# ColonRelay.net
KiCad netlist of a schematic drawn in EAGLE
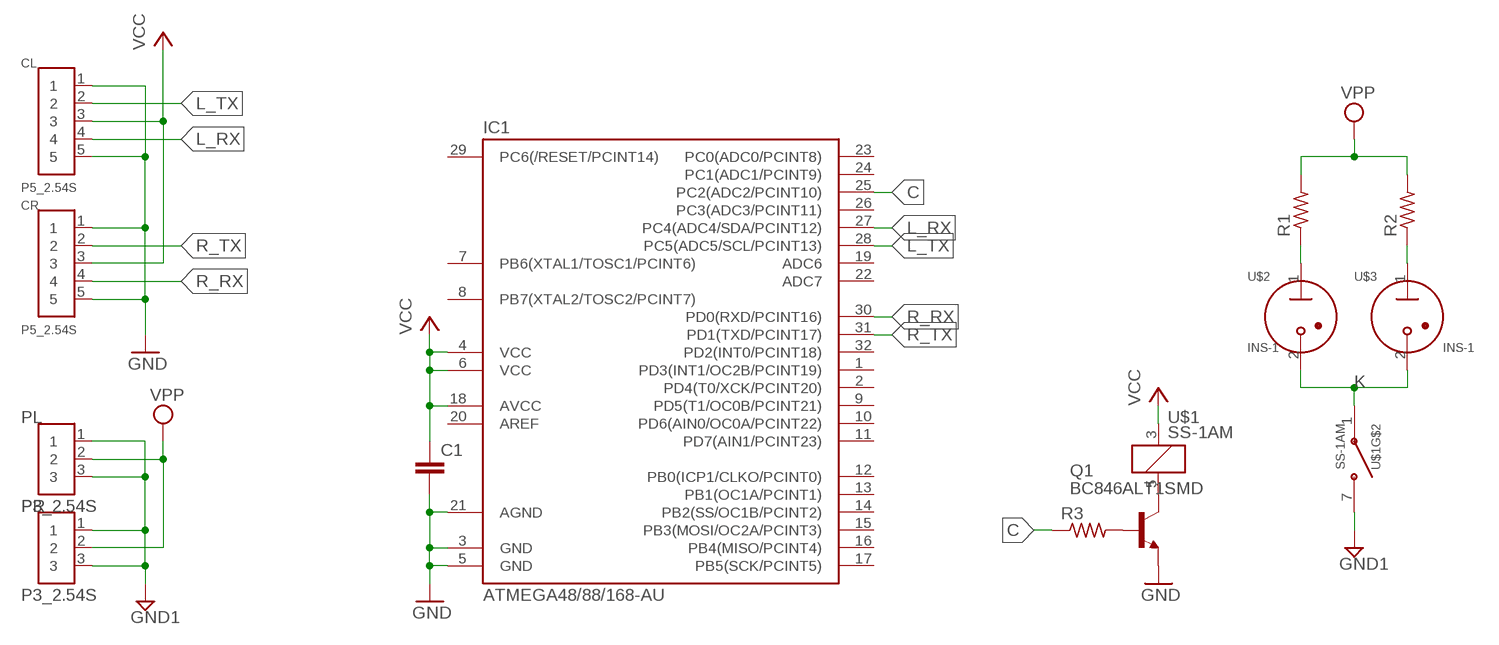
[diagram p0: schematic, sheet 1]

(export (version "E")
  (design (tool "Eeschema 10.0.6"))
  (components
    (comp (ref "C1")
      (value "C-EUC0603K")
      (footprint "eagle-import:C0603K")
      (libsource (lib "eagle-import") (part "C-EUC0603K"))
    )
    (comp (ref "CL")
      (value "P5_2.54S")
      (footprint "eagle-import:P5_2.54S")
      (libsource (lib "eagle-import") (part "P5_2.54S"))
    )
    (comp (ref "CR")
      (value "P5_2.54S")
      (footprint "eagle-import:P5_2.54S")
      (libsource (lib "eagle-import") (part "P5_2.54S"))
    )
    (comp (ref "IC1")
      (value "ATMEGA48/88/168-AU")
      (footprint "eagle-import:TQFP32-08")
      (libsource (lib "eagle-import") (part "ATMEGA48/88/168-AU"))
    )
    (comp (ref "PL")
      (value "P3_2.54S")
      (footprint "eagle-import:P3_2.54S")
      (libsource (lib "eagle-import") (part "P3_2.54S"))
    )
    (comp (ref "PR")
      (value "P3_2.54S")
      (footprint "eagle-import:P3_2.54S")
      (libsource (lib "eagle-import") (part "P3_2.54S"))
    )
    (comp (ref "Q1")
      (value "BC846ALT1SMD")
      (footprint "eagle-import:SOT23")
      (libsource (lib "eagle-import") (part "BC846SMDALT1"))
    )
    (comp (ref "R1")
      (value "R-US_R1206")
      (footprint "eagle-import:R1206")
      (libsource (lib "eagle-import") (part "R-US_R1206"))
    )
    (comp (ref "R2")
      (value "R-US_R1206")
      (footprint "eagle-import:R1206")
      (libsource (lib "eagle-import") (part "R-US_R1206"))
    )
    (comp (ref "R3")
      (value "R-US_R0603")
      (footprint "eagle-import:R0603")
      (libsource (lib "eagle-import") (part "R-US_R0603"))
    )
    (comp (ref "U$1")
      (value "SS-1AM")
      (footprint "eagle-import:SS-1____M")
      (libsource (lib "eagle-import") (part "SS-1AM"))
    )
    (comp (ref "U$2")
      (value "INS-1")
      (footprint "eagle-import:INS-1")
      (libsource (lib "eagle-import") (part "INS-1"))
    )
    (comp (ref "U$3")
      (value "INS-1")
      (footprint "eagle-import:INS-1")
      (libsource (lib "eagle-import") (part "INS-1"))
    )
  )
  (nets
    (net (code "1") (name "/K") (class "Default")
      (node (ref "U$1") (pin "1") (pinfunction "P$1_1") (pintype "bidirectional"))
      (node (ref "U$2") (pin "2") (pinfunction "C_2") (pintype "bidirectional"))
      (node (ref "U$3") (pin "2") (pinfunction "C_2") (pintype "bidirectional"))
    )
    (net (code "2") (name "C") (class "Default")
      (node (ref "IC1") (pin "25") (pinfunction "PC2(ADC2/PCINT10)_25") (pintype "bidirectional"))
      (node (ref "R3") (pin "1") (pinfunction "1_1") (pintype "passive"))
    )
    (net (code "3") (name "GND") (class "Default")
      (node (ref "C1") (pin "2") (pinfunction "2_2") (pintype "passive"))
      (node (ref "CL") (pin "1") (pinfunction "1_1") (pintype "bidirectional"))
      (node (ref "CL") (pin "5") (pinfunction "5_5") (pintype "bidirectional"))
      (node (ref "CR") (pin "1") (pinfunction "1_1") (pintype "bidirectional"))
      (node (ref "CR") (pin "5") (pinfunction "5_5") (pintype "bidirectional"))
      (node (ref "IC1") (pin "21") (pinfunction "AGND_21") (pintype "power_in"))
      (node (ref "IC1") (pin "3") (pinfunction "GND_3") (pintype "power_in"))
      (node (ref "IC1") (pin "5") (pinfunction "GND_5") (pintype "power_in"))
      (node (ref "Q1") (pin "2") (pinfunction "E_2") (pintype "passive"))
    )
    (net (code "4") (name "GND1") (class "Default")
      (node (ref "PL") (pin "1") (pinfunction "1_1") (pintype "bidirectional"))
      (node (ref "PL") (pin "3") (pinfunction "3_3") (pintype "bidirectional"))
      (node (ref "PR") (pin "1") (pinfunction "1_1") (pintype "bidirectional"))
      (node (ref "PR") (pin "3") (pinfunction "3_3") (pintype "bidirectional"))
      (node (ref "U$1") (pin "7") (pinfunction "P$2_7") (pintype "bidirectional"))
    )
    (net (code "5") (name "L_RX") (class "Default")
      (node (ref "CL") (pin "4") (pinfunction "4_4") (pintype "bidirectional"))
      (node (ref "IC1") (pin "27") (pinfunction "PC4(ADC4/SDA/PCINT12)_27") (pintype "bidirectional"))
    )
    (net (code "6") (name "L_TX") (class "Default")
      (node (ref "CL") (pin "2") (pinfunction "2_2") (pintype "bidirectional"))
      (node (ref "IC1") (pin "28") (pinfunction "PC5(ADC5/SCL/PCINT13)_28") (pintype "bidirectional"))
    )
    (net (code "7") (name "Net-(Q1-B)") (class "Default")
      (node (ref "Q1") (pin "1") (pinfunction "B_1") (pintype "passive"))
      (node (ref "R3") (pin "2") (pinfunction "2_2") (pintype "passive"))
    )
    (net (code "8") (name "Net-(Q1-C)") (class "Default")
      (node (ref "Q1") (pin "3") (pinfunction "C_3") (pintype "passive"))
      (node (ref "U$1") (pin "5") (pinfunction "2_5") (pintype "passive"))
    )
    (net (code "9") (name "Net-(U$2-A)") (class "Default")
      (node (ref "R1") (pin "1") (pinfunction "1_1") (pintype "passive"))
      (node (ref "U$2") (pin "1") (pinfunction "A_1") (pintype "bidirectional"))
    )
    (net (code "10") (name "Net-(U$3-A)") (class "Default")
      (node (ref "R2") (pin "1") (pinfunction "1_1") (pintype "passive"))
      (node (ref "U$3") (pin "1") (pinfunction "A_1") (pintype "bidirectional"))
    )
    (net (code "11") (name "R_RX") (class "Default")
      (node (ref "CR") (pin "4") (pinfunction "4_4") (pintype "bidirectional"))
      (node (ref "IC1") (pin "30") (pinfunction "PD0(RXD/PCINT16)_30") (pintype "bidirectional"))
    )
    (net (code "12") (name "R_TX") (class "Default")
      (node (ref "CR") (pin "2") (pinfunction "2_2") (pintype "bidirectional"))
      (node (ref "IC1") (pin "31") (pinfunction "PD1(TXD/PCINT17)_31") (pintype "bidirectional"))
    )
    (net (code "13") (name "VCC") (class "Default")
      (node (ref "C1") (pin "1") (pinfunction "1_1") (pintype "passive"))
      (node (ref "CL") (pin "3") (pinfunction "3_3") (pintype "bidirectional"))
      (node (ref "CR") (pin "3") (pinfunction "3_3") (pintype "bidirectional"))
      (node (ref "IC1") (pin "18") (pinfunction "AVCC_18") (pintype "passive"))
      (node (ref "IC1") (pin "4") (pinfunction "VCC_4") (pintype "power_in"))
      (node (ref "IC1") (pin "6") (pinfunction "VCC_6") (pintype "power_in"))
      (node (ref "U$1") (pin "3") (pinfunction "1_3") (pintype "passive"))
    )
    (net (code "14") (name "VPP") (class "Default")
      (node (ref "PL") (pin "2") (pinfunction "2_2") (pintype "bidirectional"))
      (node (ref "PR") (pin "2") (pinfunction "2_2") (pintype "bidirectional"))
      (node (ref "R1") (pin "2") (pinfunction "2_2") (pintype "passive"))
      (node (ref "R2") (pin "2") (pinfunction "2_2") (pintype "passive"))
    )
    (net (code "15") (name "unconnected-(IC1-ADC6-Pad19)") (class "Default")
      (node (ref "IC1") (pin "19") (pinfunction "ADC6_19") (pintype "passive"))
    )
    (net (code "16") (name "unconnected-(IC1-ADC7-Pad22)") (class "Default")
      (node (ref "IC1") (pin "22") (pinfunction "ADC7_22") (pintype "passive"))
    )
    (net (code "17") (name "unconnected-(IC1-AREF-Pad20)") (class "Default")
      (node (ref "IC1") (pin "20") (pinfunction "AREF_20") (pintype "passive"))
    )
    (net (code "18") (name "unconnected-(IC1-PB0(ICP1{slash}CLKO{slash}PCINT0)-Pad12)") (class "Default")
      (node (ref "IC1") (pin "12") (pinfunction "PB0(ICP1/CLKO/PCINT0)_12") (pintype "bidirectional"))
    )
    (net (code "19") (name "unconnected-(IC1-PB1(OC1A{slash}PCINT1)-Pad13)") (class "Default")
      (node (ref "IC1") (pin "13") (pinfunction "PB1(OC1A/PCINT1)_13") (pintype "bidirectional"))
    )
    (net (code "20") (name "unconnected-(IC1-PB2(SS{slash}OC1B{slash}PCINT2)-Pad14)") (class "Default")
      (node (ref "IC1") (pin "14") (pinfunction "PB2(SS/OC1B/PCINT2)_14") (pintype "bidirectional"))
    )
    (net (code "21") (name "unconnected-(IC1-PB3(MOSI{slash}OC2A{slash}PCINT3)-Pad15)") (class "Default")
      (node (ref "IC1") (pin "15") (pinfunction "PB3(MOSI/OC2A/PCINT3)_15") (pintype "bidirectional"))
    )
    (net (code "22") (name "unconnected-(IC1-PB4(MISO{slash}PCINT4)-Pad16)") (class "Default")
      (node (ref "IC1") (pin "16") (pinfunction "PB4(MISO/PCINT4)_16") (pintype "bidirectional"))
    )
    (net (code "23") (name "unconnected-(IC1-PB5(SCK{slash}PCINT5)-Pad17)") (class "Default")
      (node (ref "IC1") (pin "17") (pinfunction "PB5(SCK/PCINT5)_17") (pintype "bidirectional"))
    )
    (net (code "24") (name "unconnected-(IC1-PB6(XTAL1{slash}TOSC1{slash}PCINT6)-Pad7)") (class "Default")
      (node (ref "IC1") (pin "7") (pinfunction "PB6(XTAL1/TOSC1/PCINT6)_7") (pintype "bidirectional"))
    )
    (net (code "25") (name "unconnected-(IC1-PB7(XTAL2{slash}TOSC2{slash}PCINT7)-Pad8)") (class "Default")
      (node (ref "IC1") (pin "8") (pinfunction "PB7(XTAL2/TOSC2/PCINT7)_8") (pintype "bidirectional"))
    )
    (net (code "26") (name "unconnected-(IC1-PC0(ADC0{slash}PCINT8)-Pad23)") (class "Default")
      (node (ref "IC1") (pin "23") (pinfunction "PC0(ADC0/PCINT8)_23") (pintype "bidirectional"))
    )
    (net (code "27") (name "unconnected-(IC1-PC1(ADC1{slash}PCINT9)-Pad24)") (class "Default")
      (node (ref "IC1") (pin "24") (pinfunction "PC1(ADC1/PCINT9)_24") (pintype "bidirectional"))
    )
    (net (code "28") (name "unconnected-(IC1-PC3(ADC3{slash}PCINT11)-Pad26)") (class "Default")
      (node (ref "IC1") (pin "26") (pinfunction "PC3(ADC3/PCINT11)_26") (pintype "bidirectional"))
    )
    (net (code "29") (name "unconnected-(IC1-PC6({slash}RESET{slash}PCINT14)-Pad29)") (class "Default")
      (node (ref "IC1") (pin "29") (pinfunction "PC6(/RESET/PCINT14)_29") (pintype "bidirectional"))
    )
    (net (code "30") (name "unconnected-(IC1-PD2(INT0{slash}PCINT18)-Pad32)") (class "Default")
      (node (ref "IC1") (pin "32") (pinfunction "PD2(INT0/PCINT18)_32") (pintype "bidirectional"))
    )
    (net (code "31") (name "unconnected-(IC1-PD3(INT1{slash}OC2B{slash}PCINT19)-Pad1)") (class "Default")
      (node (ref "IC1") (pin "1") (pinfunction "PD3(INT1/OC2B/PCINT19)_1") (pintype "bidirectional"))
    )
    (net (code "32") (name "unconnected-(IC1-PD4(T0{slash}XCK{slash}PCINT20)-Pad2)") (class "Default")
      (node (ref "IC1") (pin "2") (pinfunction "PD4(T0/XCK/PCINT20)_2") (pintype "bidirectional"))
    )
    (net (code "33") (name "unconnected-(IC1-PD5(T1{slash}OC0B{slash}PCINT21)-Pad9)") (class "Default")
      (node (ref "IC1") (pin "9") (pinfunction "PD5(T1/OC0B/PCINT21)_9") (pintype "bidirectional"))
    )
    (net (code "34") (name "unconnected-(IC1-PD6(AIN0{slash}OC0A{slash}PCINT22)-Pad10)") (class "Default")
      (node (ref "IC1") (pin "10") (pinfunction "PD6(AIN0/OC0A/PCINT22)_10") (pintype "bidirectional"))
    )
    (net (code "35") (name "unconnected-(IC1-PD7(AIN1{slash}PCINT23)-Pad11)") (class "Default")
      (node (ref "IC1") (pin "11") (pinfunction "PD7(AIN1/PCINT23)_11") (pintype "bidirectional"))
    )
  )
)
